# power.net
KiCad netlist of a schematic drawn in Altium Designer
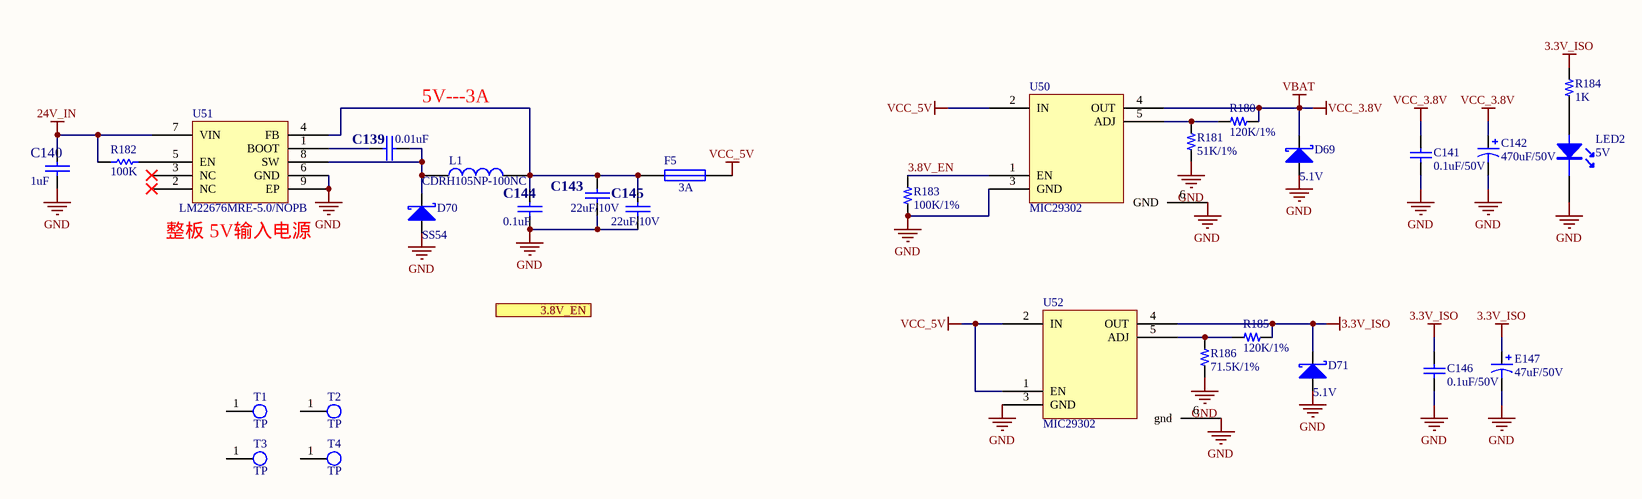
[diagram p0: power.SchDoc]

(export (version "E")
  (design (tool "Eeschema 10.0.6"))
  (components
    (comp (ref "C139")
      (value "0.01uF")
      (footprint "0603C")
      (description "Capacitor")
      (libsource (lib "*") (part "CAP"))
    )
    (comp (ref "C140")
      (value "1uF")
      (footprint "0603C")
      (description "Capacitor")
      (libsource (lib "*") (part "CAP"))
    )
    (comp (ref "C141")
      (value "0.1uF/50V")
      (footprint "0603C")
      (description "Capacitor")
      (fields (field (name "PUBLISHER") "Altium Limited"))
      (libsource (lib "Miscellaneous Devices") (part "Cap"))
    )
    (comp (ref "C142")
      (value "470uF/50V")
      (footprint "Φ10×10")
      (description "Polarized Capacitor (Radial)")
      (fields (field (name "PUBLISHER") "Altium Limited"))
      (libsource (lib "Miscellaneous Devices") (part "Cap Pol1"))
    )
    (comp (ref "C143")
      (value "22uF/10V")
      (footprint "1210C")
      (description "Capacitor")
      (libsource (lib "*") (part "CAP"))
    )
    (comp (ref "C144")
      (value "0.1uF")
      (footprint "0603C")
      (description "Capacitor")
      (libsource (lib "*") (part "CAP"))
    )
    (comp (ref "C145")
      (value "22uF/10V")
      (footprint "1210C")
      (description "Capacitor")
      (libsource (lib "*") (part "CAP"))
    )
    (comp (ref "C146")
      (value "0.1uF/50V")
      (footprint "0603C")
      (description "Capacitor")
      (fields (field (name "PUBLISHER") "Altium Limited"))
      (libsource (lib "Miscellaneous Devices") (part "Cap"))
    )
    (comp (ref "D69")
      (value "5.1V")
      (footprint "SMA")
      (description "Schottky Diode")
      (libsource (lib "*") (part "DIODE S"))
    )
    (comp (ref "D70")
      (value "SS54")
      (footprint "SMC")
      (description "Schottky Diode")
      (libsource (lib "*") (part "DIODE S"))
    )
    (comp (ref "D71")
      (value "5.1V")
      (footprint "SMA")
      (description "Schottky Diode")
      (libsource (lib "*") (part "DIODE S"))
    )
    (comp (ref "E147")
      (value "47uF/50V")
      (footprint "Φ10×10")
      (description "Polarized Capacitor (Radial)")
      (fields (field (name "PUBLISHER") "Altium Limited"))
      (libsource (lib "Miscellaneous Devices") (part "Cap Pol1"))
    )
    (comp (ref "F5")
      (value "3A")
      (footprint "1812-F")
      (description "Fuse")
      (fields (field (name "PUBLISHER") "Altium Limited"))
      (libsource (lib "Miscellaneous Devices") (part "Fuse 1"))
    )
    (comp (ref "L1") (value "CDRH105NP-100NC") (footprint "CDRH105") (libsource (lib "*") (part "INDUCTOR")))
    (comp (ref "LED2") (value "5V") (footprint "0603LED") (libsource (lib "*") (part "LED")))
    (comp (ref "R180")
      (value "120K/1%")
      (footprint "0603R")
      (description "R")
      (libsource (lib "JRJ_1") (part "R"))
    )
    (comp (ref "R181")
      (value "51K/1%")
      (footprint "0603R")
      (description "R")
      (libsource (lib "JRJ_1") (part "R"))
    )
    (comp (ref "R182")
      (value "100K")
      (footprint "0603R")
      (description "Resistor")
      (fields (field (name "PUBLISHER") "Altium Limited"))
      (libsource (lib "Miscellaneous Devices") (part "Res1"))
    )
    (comp (ref "R183")
      (value "100K/1%")
      (footprint "0603R")
      (description "R")
      (libsource (lib "JRJ_1") (part "R"))
    )
    (comp (ref "R184")
      (value "1K")
      (footprint "0603R")
      (description "R")
      (libsource (lib "JRJ_1") (part "R"))
    )
    (comp (ref "R185")
      (value "120K/1%")
      (footprint "0603R")
      (description "R")
      (libsource (lib "JRJ_1") (part "R"))
    )
    (comp (ref "R186")
      (value "71.5K/1%")
      (footprint "0603R")
      (description "R")
      (libsource (lib "JRJ_1") (part "R"))
    )
    (comp (ref "T1") (value "TP") (footprint "M3") (libsource (lib "Schlib_20110825") (part "TP")))
    (comp (ref "T2") (value "TP") (footprint "M3") (libsource (lib "Schlib_20110825") (part "TP")))
    (comp (ref "T3") (value "TP") (footprint "M3") (libsource (lib "Schlib_20110825") (part "TP")))
    (comp (ref "T4") (value "TP") (footprint "M3") (libsource (lib "Schlib_20110825") (part "TP")))
    (comp (ref "U50")
      (value "MIC29302")
      (footprint "TO228P1435X457-6N")
      (libsource (lib "power") (part "MIC29302"))
    )
    (comp (ref "U51")
      (value "LM22676MRE-5.0/NOPB")
      (footprint "SOP127P600X168_HS-8N")
      (libsource (lib "Schlib1") (part "LM22676MR-5.0"))
    )
    (comp (ref "U52")
      (value "MIC29302")
      (footprint "TO228P1435X457-6N")
      (libsource (lib "power") (part "MIC29302"))
    )
  )
  (nets
    (net (code "1") (name "/3.8V_EN") (class "Default")
      (node (ref "R183") (pin "2") (pintype "passive"))
      (node (ref "U50") (pin "1") (pinfunction "EN_1") (pintype "passive"))
    )
    (net (code "2") (name "3.3V_ISO") (class "Default")
      (node (ref "C146") (pin "2") (pinfunction "2_2") (pintype "passive"))
      (node (ref "D71") (pin "2") (pinfunction "K_2") (pintype "passive"))
      (node (ref "E147") (pin "1") (pinfunction "1_1") (pintype "passive"))
      (node (ref "R184") (pin "2") (pintype "passive"))
      (node (ref "R185") (pin "1") (pintype "passive"))
      (node (ref "U52") (pin "4") (pinfunction "OUT_4") (pintype "passive"))
    )
    (net (code "3") (name "24V_IN") (class "Default")
      (node (ref "C140") (pin "2") (pinfunction "2_2") (pintype "passive"))
      (node (ref "R182") (pin "2") (pinfunction "2_2") (pintype "passive"))
      (node (ref "U51") (pin "7") (pinfunction "VIN_7") (pintype "passive"))
    )
    (net (code "4") (name "GND") (class "Default")
      (node (ref "C140") (pin "1") (pinfunction "1_1") (pintype "passive"))
      (node (ref "C141") (pin "1") (pinfunction "1_1") (pintype "passive"))
      (node (ref "C142") (pin "2") (pinfunction "2_2") (pintype "passive"))
      (node (ref "C143") (pin "2") (pinfunction "2_2") (pintype "passive"))
      (node (ref "C144") (pin "2") (pinfunction "2_2") (pintype "passive"))
      (node (ref "C145") (pin "2") (pinfunction "2_2") (pintype "passive"))
      (node (ref "C146") (pin "1") (pinfunction "1_1") (pintype "passive"))
      (node (ref "D69") (pin "1") (pinfunction "A_1") (pintype "passive"))
      (node (ref "D70") (pin "1") (pinfunction "A_1") (pintype "passive"))
      (node (ref "D71") (pin "1") (pinfunction "A_1") (pintype "passive"))
      (node (ref "E147") (pin "2") (pinfunction "2_2") (pintype "passive"))
      (node (ref "LED2") (pin "2") (pinfunction "2_2") (pintype "passive"))
      (node (ref "R181") (pin "1") (pintype "passive"))
      (node (ref "R183") (pin "1") (pintype "passive"))
      (node (ref "R186") (pin "1") (pintype "passive"))
      (node (ref "U50") (pin "3") (pinfunction "GND_3") (pintype "passive"))
      (node (ref "U50") (pin "6") (pinfunction "GND_6") (pintype "passive"))
      (node (ref "U51") (pin "6") (pinfunction "GND_6") (pintype "passive"))
      (node (ref "U51") (pin "9") (pinfunction "EP_9") (pintype "passive"))
      (node (ref "U52") (pin "3") (pinfunction "GND_3") (pintype "passive"))
      (node (ref "U52") (pin "6") (pinfunction "GND_6") (pintype "passive"))
    )
    (net (code "5") (name "Net-(D70-K)") (class "Default")
      (node (ref "C139") (pin "1") (pinfunction "1_1") (pintype "passive"))
      (node (ref "D70") (pin "2") (pinfunction "K_2") (pintype "passive"))
      (node (ref "L1") (pin "1") (pinfunction "1_1") (pintype "passive"))
      (node (ref "U51") (pin "8") (pinfunction "SW_8") (pintype "passive"))
    )
    (net (code "6") (name "Net-(LED2-Pad1)") (class "Default")
      (node (ref "LED2") (pin "1") (pinfunction "1_1") (pintype "passive"))
      (node (ref "R184") (pin "1") (pintype "passive"))
    )
    (net (code "7") (name "Net-(U50-ADJ)") (class "Default")
      (node (ref "R180") (pin "2") (pintype "passive"))
      (node (ref "R181") (pin "2") (pintype "passive"))
      (node (ref "U50") (pin "5") (pinfunction "ADJ_5") (pintype "passive"))
    )
    (net (code "8") (name "Net-(U51-BOOT)") (class "Default")
      (node (ref "C139") (pin "2") (pinfunction "2_2") (pintype "passive"))
      (node (ref "U51") (pin "1") (pinfunction "BOOT_1") (pintype "passive"))
    )
    (net (code "9") (name "Net-(U51-EN)") (class "Default")
      (node (ref "R182") (pin "1") (pinfunction "1_1") (pintype "passive"))
      (node (ref "U51") (pin "5") (pinfunction "EN_5") (pintype "passive"))
    )
    (net (code "10") (name "Net-(U51-FB)") (class "Default")
      (node (ref "C143") (pin "1") (pinfunction "1_1") (pintype "passive"))
      (node (ref "C144") (pin "1") (pinfunction "1_1") (pintype "passive"))
      (node (ref "C145") (pin "1") (pinfunction "1_1") (pintype "passive"))
      (node (ref "F5") (pin "1") (pinfunction "1_1") (pintype "passive"))
      (node (ref "L1") (pin "2") (pinfunction "2_2") (pintype "passive"))
      (node (ref "U51") (pin "4") (pinfunction "FB_4") (pintype "passive"))
    )
    (net (code "11") (name "Net-(U52-ADJ)") (class "Default")
      (node (ref "R185") (pin "2") (pintype "passive"))
      (node (ref "R186") (pin "2") (pintype "passive"))
      (node (ref "U52") (pin "5") (pinfunction "ADJ_5") (pintype "passive"))
    )
    (net (code "12") (name "VBAT") (class "Default")
      (node (ref "C141") (pin "2") (pinfunction "2_2") (pintype "passive"))
      (node (ref "C142") (pin "1") (pinfunction "1_1") (pintype "passive"))
      (node (ref "D69") (pin "2") (pinfunction "K_2") (pintype "passive"))
      (node (ref "R180") (pin "1") (pintype "passive"))
      (node (ref "U50") (pin "4") (pinfunction "OUT_4") (pintype "passive"))
    )
    (net (code "13") (name "VCC_5V") (class "Default")
      (node (ref "F5") (pin "2") (pinfunction "2_2") (pintype "passive"))
      (node (ref "U50") (pin "2") (pinfunction "IN_2") (pintype "passive"))
      (node (ref "U52") (pin "1") (pinfunction "EN_1") (pintype "passive"))
      (node (ref "U52") (pin "2") (pinfunction "IN_2") (pintype "passive"))
    )
    (net (code "14") (name "unconnected-(T1-Pad1)") (class "Default")
      (node (ref "T1") (pin "1") (pintype "passive"))
    )
    (net (code "15") (name "unconnected-(T2-Pad1)") (class "Default")
      (node (ref "T2") (pin "1") (pintype "passive"))
    )
    (net (code "16") (name "unconnected-(T3-Pad1)") (class "Default")
      (node (ref "T3") (pin "1") (pintype "passive"))
    )
    (net (code "17") (name "unconnected-(T4-Pad1)") (class "Default")
      (node (ref "T4") (pin "1") (pintype "passive"))
    )
    (net (code "18") (name "unconnected-(U51-NC-Pad2)") (class "Default")
      (node (ref "U51") (pin "2") (pinfunction "NC_2") (pintype "passive+no_connect"))
    )
    (net (code "19") (name "unconnected-(U51-NC-Pad3)") (class "Default")
      (node (ref "U51") (pin "3") (pinfunction "NC_3") (pintype "passive+no_connect"))
    )
  )
)
